# Basic_OCTA-MINI.net
KiCad netlist of a schematic drawn in EAGLE
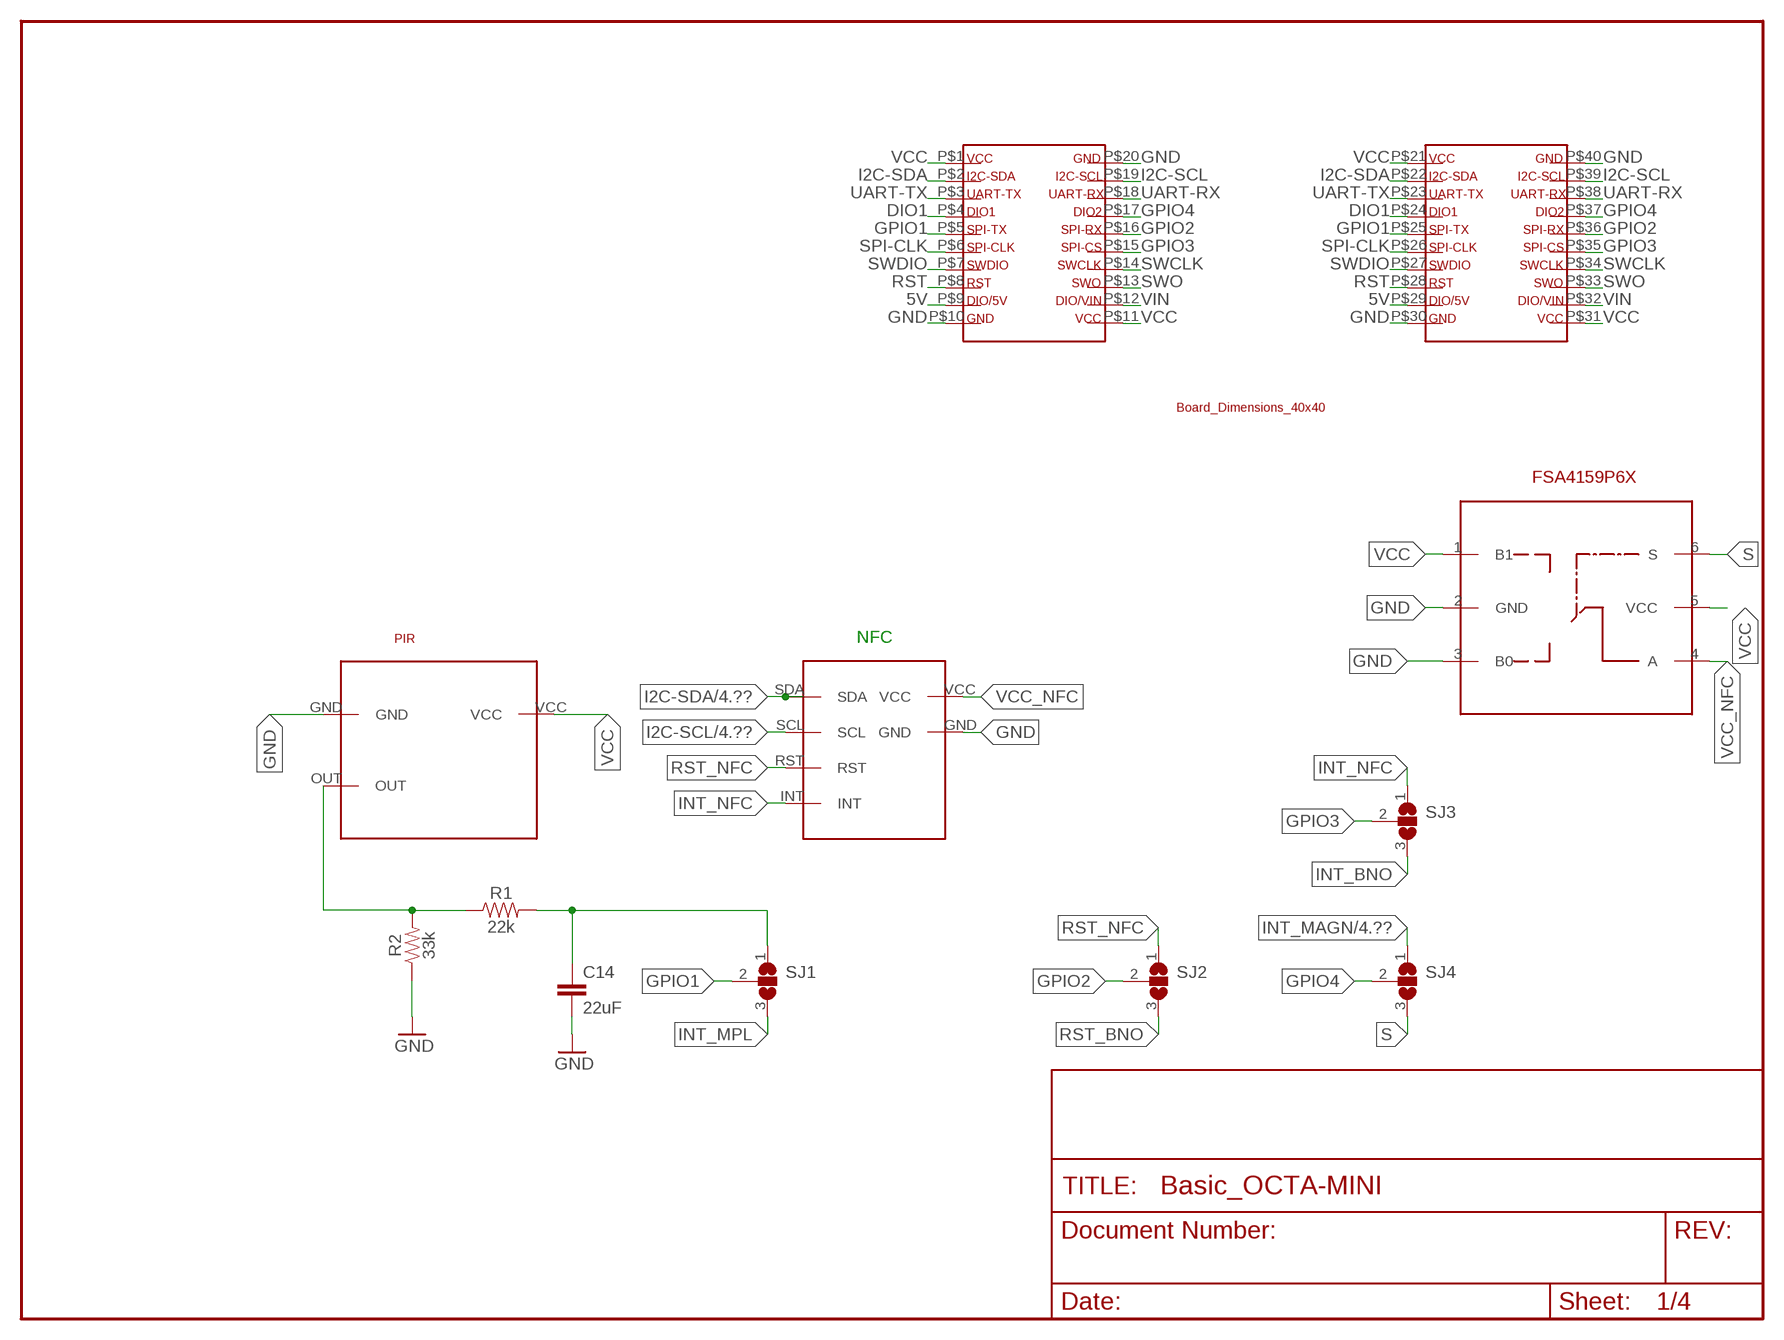
[diagram p0: schematic, sheet 1]
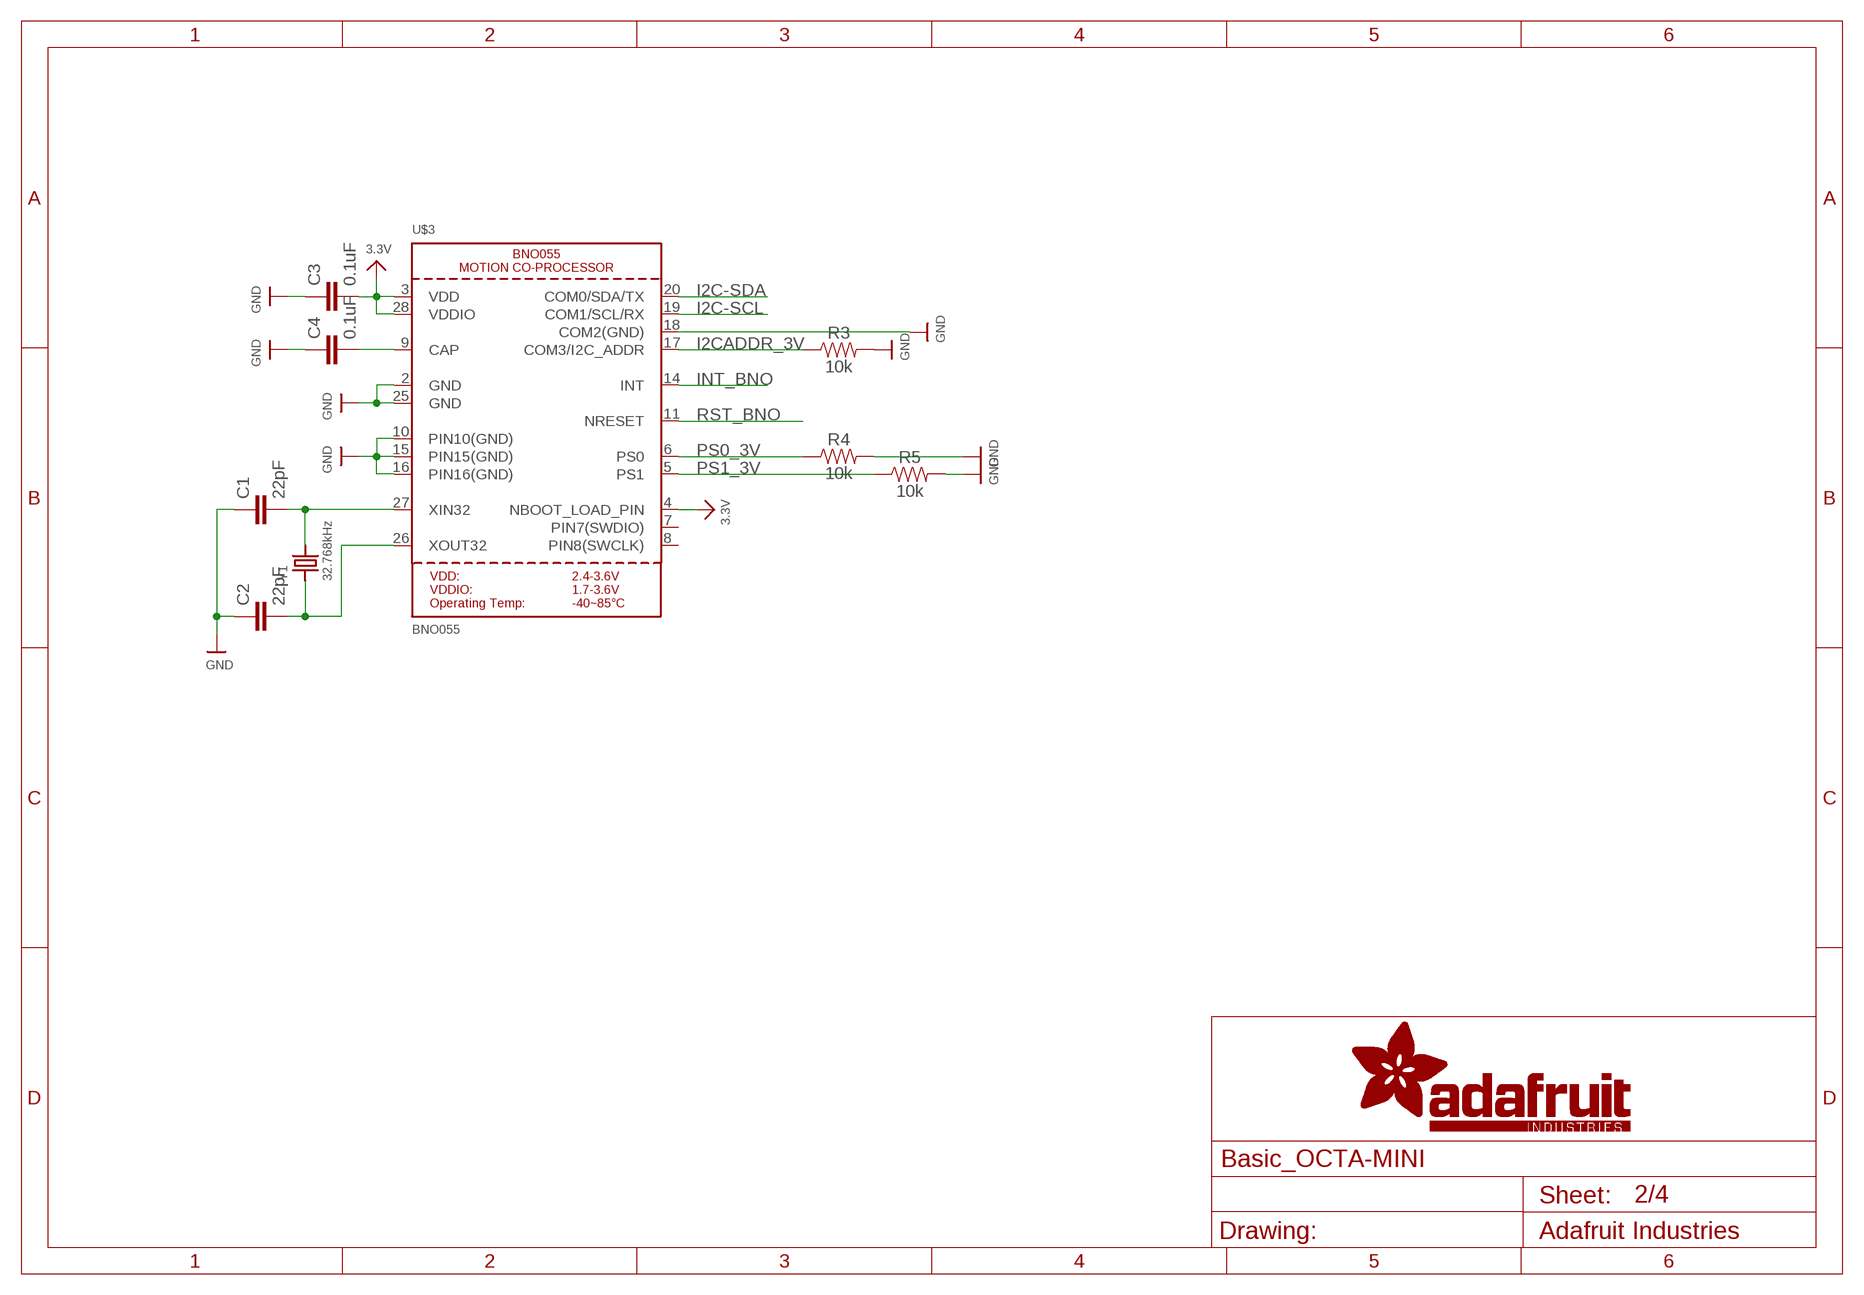
[diagram p1: schematic, sheet 2]
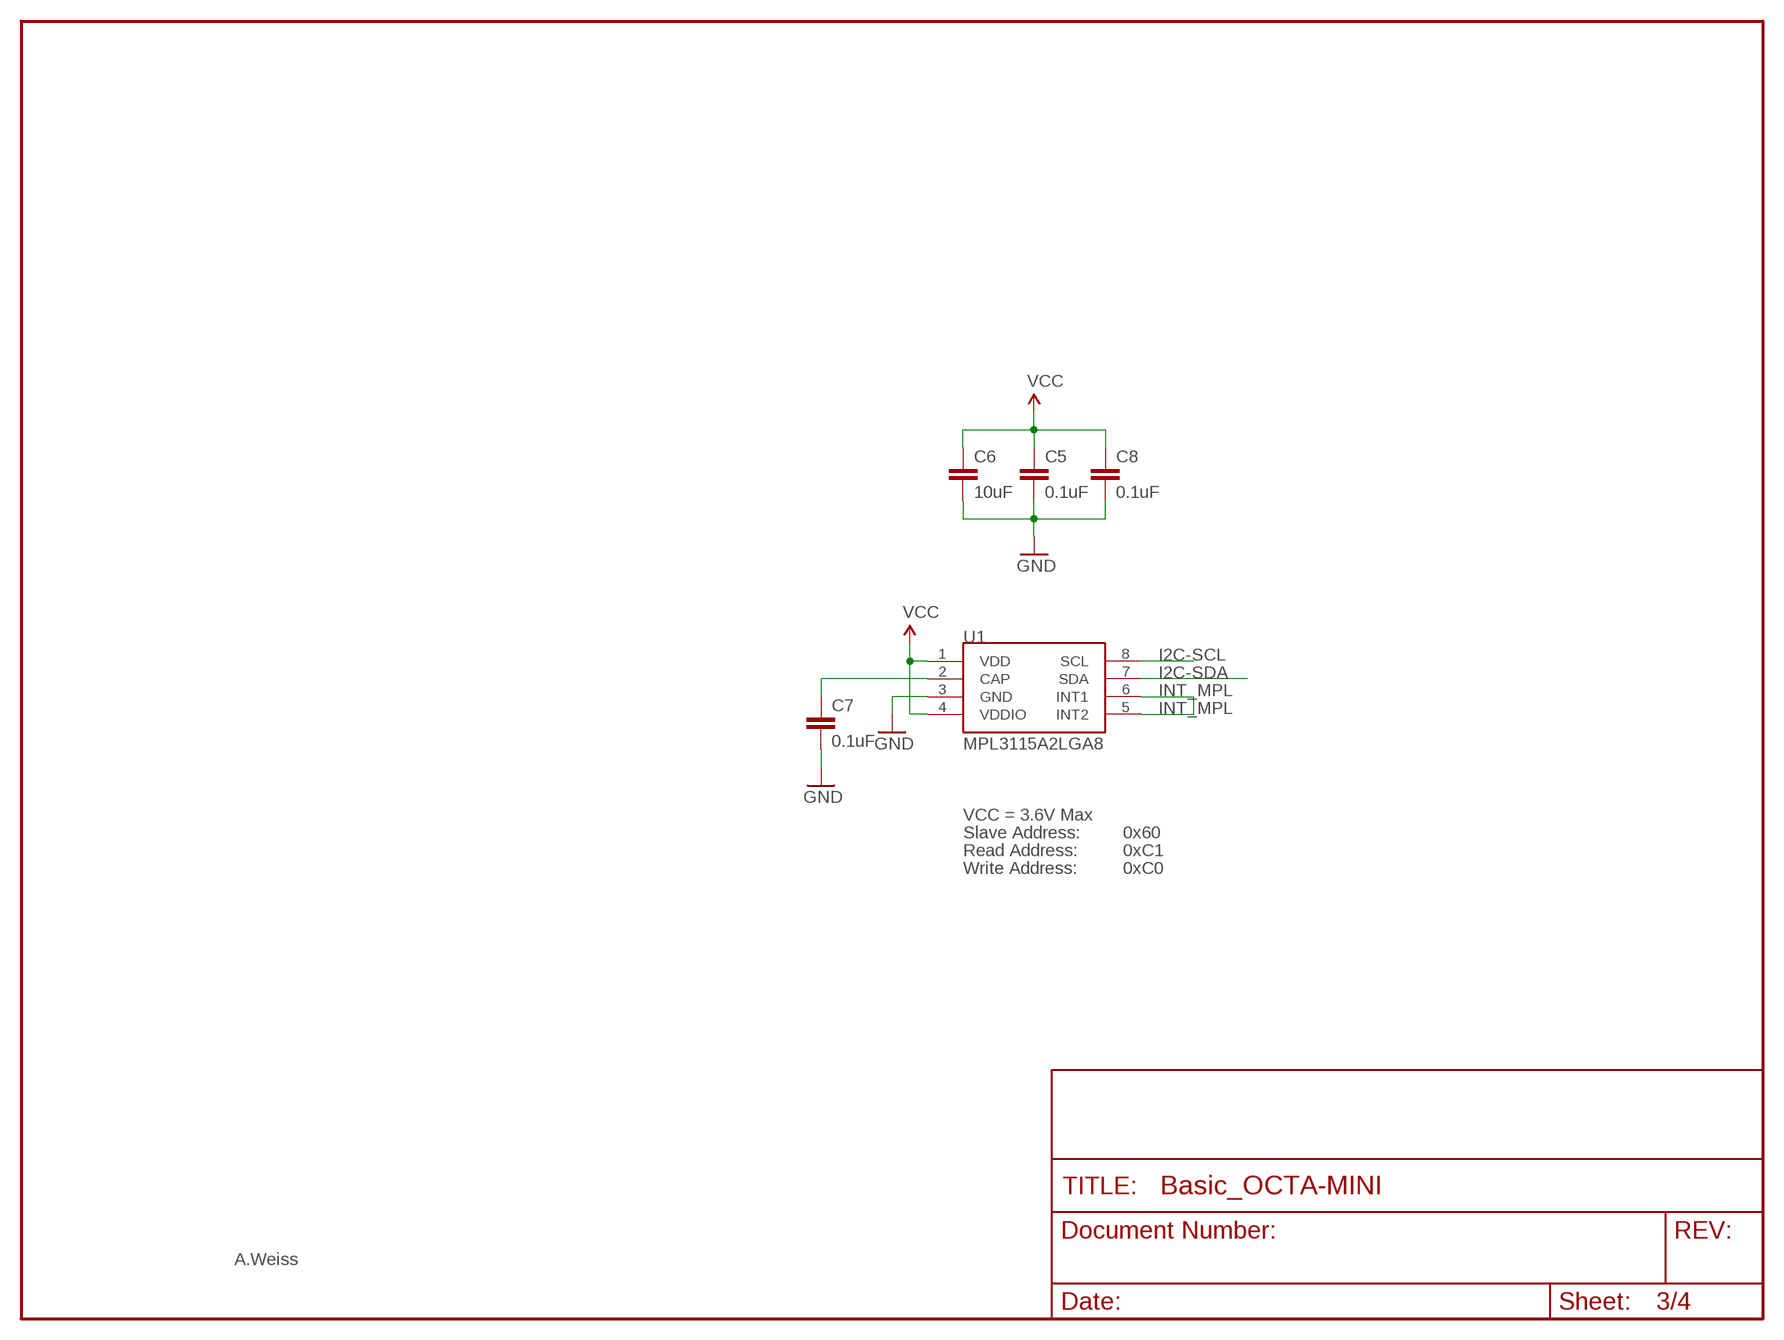
[diagram p2: schematic, sheet 3]
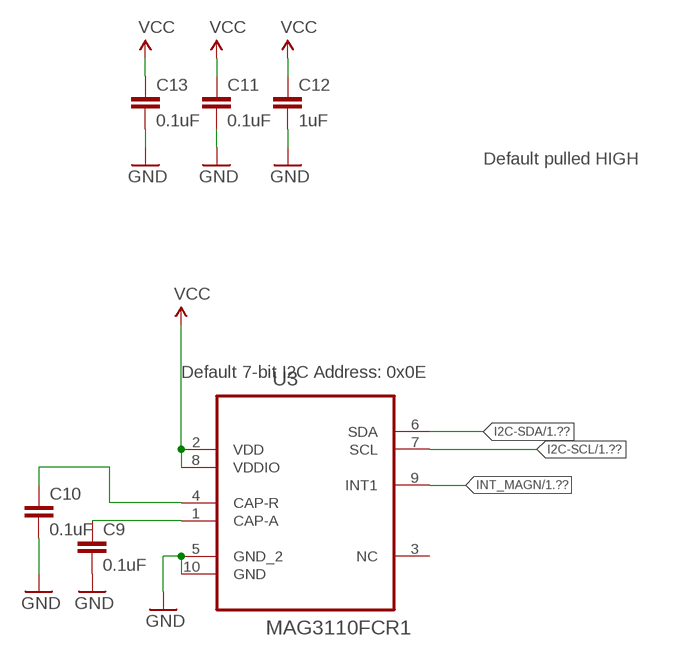
[diagram p3: schematic, sheet 4]

(export (version "E")
  (design (tool "Eeschema 10.0.6"))
  (components
    (comp (ref "C9")
      (value "0.1uF")
      (footprint "eagle-import:0603-CAP")
      (libsource (lib "eagle-import") (part "CAP0603-CAP"))
    )
    (comp (ref "C10")
      (value "0.1uF")
      (footprint "eagle-import:0603-CAP")
      (libsource (lib "eagle-import") (part "CAP0603-CAP"))
    )
    (comp (ref "C11")
      (value "0.1uF")
      (footprint "eagle-import:0603-CAP")
      (libsource (lib "eagle-import") (part "CAP0603-CAP"))
    )
    (comp (ref "C12")
      (value "1uF")
      (footprint "eagle-import:0603-CAP")
      (libsource (lib "eagle-import") (part "CAP0603-CAP"))
    )
    (comp (ref "C13")
      (value "0.1uF")
      (footprint "eagle-import:0603-CAP")
      (libsource (lib "eagle-import") (part "CAP0603-CAP"))
    )
    (comp (ref "U3")
      (value "MAG3110FCR1")
      (footprint "eagle-import:DFN200X200X90-10N")
      (libsource (lib "eagle-import") (part "MAG3110FCR1"))
    )
    (comp (ref "C5")
      (value "0.1uF")
      (footprint "eagle-import:0603")
      (libsource (lib "eagle-import") (part "0.1UF-0603-25V-(+80/-20%)"))
    )
    (comp (ref "C6")
      (value "10uF")
      (footprint "eagle-import:0603")
      (libsource (lib "eagle-import") (part "10UF-0603-6.3V-20%"))
    )
    (comp (ref "C7")
      (value "0.1uF")
      (footprint "eagle-import:0603")
      (libsource (lib "eagle-import") (part "0.1UF-0603-25V-(+80/-20%)"))
    )
    (comp (ref "C8")
      (value "0.1uF")
      (footprint "eagle-import:0603")
      (libsource (lib "eagle-import") (part "0.1UF-0603-25V-(+80/-20%)"))
    )
    (comp (ref "U1")
      (value "MPL3115A2LGA8")
      (footprint "eagle-import:LGA8")
      (libsource (lib "eagle-import") (part "MPL3115A2LGA8"))
    )
    (comp (ref "C1")
      (value "22pF")
      (footprint "eagle-import:0603")
      (libsource (lib "eagle-import") (part "22PF-0603-50V-5%"))
    )
    (comp (ref "C2")
      (value "22pF")
      (footprint "eagle-import:0603")
      (libsource (lib "eagle-import") (part "22PF-0603-50V-5%"))
    )
    (comp (ref "C3")
      (value "0.1uF")
      (footprint "eagle-import:0603")
      (libsource (lib "eagle-import") (part "0.1UF-0603-25V-(+80/-20%)"))
    )
    (comp (ref "C4")
      (value "0.1uF")
      (footprint "eagle-import:0603")
      (libsource (lib "eagle-import") (part "0.1UF-0603-25V-(+80/-20%)"))
    )
    (comp (ref "R3")
      (value "10k")
      (footprint "eagle-import:0603")
      (libsource (lib "eagle-import") (part "10KOHM-0603-1/10W-1%"))
    )
    (comp (ref "R4")
      (value "10k")
      (footprint "eagle-import:0603")
      (libsource (lib "eagle-import") (part "10KOHM-0603-1/10W-1%"))
    )
    (comp (ref "R5")
      (value "10k")
      (footprint "eagle-import:0603")
      (libsource (lib "eagle-import") (part "10KOHM-0603-1/10W-1%"))
    )
    (comp (ref "U$3")
      (value "BNO055")
      (footprint "eagle-import:BNO055")
      (libsource (lib "eagle-import") (part "BNO055"))
    )
    (comp (ref "Y1")
      (value "32.768kHz")
      (footprint "eagle-import:CRYSTAL_8X3.8")
      (libsource (lib "eagle-import") (part "CRYSTAL8.0X3.8"))
    )
    (comp (ref "C14")
      (value "22uF")
      (footprint "eagle-import:0805")
      (libsource (lib "eagle-import") (part "22UF-0805-6.3V-20%"))
    )
    (comp (ref "R1")
      (value "22k")
      (footprint "eagle-import:0603")
      (libsource (lib "eagle-import") (part "22KOHM-0603-1/10W-1%"))
    )
    (comp (ref "R2")
      (value "33k")
      (footprint "eagle-import:0603")
      (libsource (lib "eagle-import") (part "33KOHM-0603-1/10W-1%"))
    )
    (comp (ref "SJ1")
      (value "SJ2W")
      (footprint "eagle-import:SJ_2")
      (libsource (lib "eagle-import") (part "SJ2W"))
    )
    (comp (ref "SJ2")
      (value "SJ2W")
      (footprint "eagle-import:SJ_2")
      (libsource (lib "eagle-import") (part "SJ2W"))
    )
    (comp (ref "SJ3")
      (value "SJ2W")
      (footprint "eagle-import:SJ_2")
      (libsource (lib "eagle-import") (part "SJ2W"))
    )
    (comp (ref "SJ4")
      (value "SJ2W")
      (footprint "eagle-import:SJ_2")
      (libsource (lib "eagle-import") (part "SJ2W"))
    )
    (comp (ref "U$2")
      (value "BOARD-DIMENSIONS-40X40")
      (footprint "eagle-import:BOARD-DIMENSIONS-40X40")
      (libsource (lib "eagle-import") (part "BOARD-DIMENSIONS-40X40"))
    )
    (comp (ref "U$9")
      (value "PIR")
      (footprint "eagle-import:PIR")
      (libsource (lib "eagle-import") (part "PIR"))
    )
    (comp (ref "U$10")
      (value "NFC")
      (footprint "eagle-import:NFC")
      (libsource (lib "eagle-import") (part "NFC"))
    )
    (comp (ref "U$17")
      (value "FSA4159P6X")
      (footprint "eagle-import:SOT65P210X100-6N")
      (libsource (lib "eagle-import") (part "FSA4159P6X"))
    )
  )
  (nets
    (net (code "1") (name "5V") (class "Default")
      (node (ref "U$2") (pin "P$29") (pinfunction "P$29_P$29") (pintype "bidirectional"))
      (node (ref "U$2") (pin "P$9") (pinfunction "P$9_P$9") (pintype "bidirectional"))
    )
    (net (code "2") (name "DIO1") (class "Default")
      (node (ref "U$2") (pin "P$24") (pinfunction "P$24_P$24") (pintype "bidirectional"))
      (node (ref "U$2") (pin "P$4") (pinfunction "P$4_P$4") (pintype "bidirectional"))
    )
    (net (code "3") (name "GND") (class "Default")
      (node (ref "C1") (pin "1") (pinfunction "1_1") (pintype "passive"))
      (node (ref "C10") (pin "2") (pinfunction "2_2") (pintype "passive"))
      (node (ref "C11") (pin "2") (pinfunction "2_2") (pintype "passive"))
      (node (ref "C12") (pin "2") (pinfunction "2_2") (pintype "passive"))
      (node (ref "C13") (pin "2") (pinfunction "2_2") (pintype "passive"))
      (node (ref "C14") (pin "2") (pinfunction "2_2") (pintype "passive"))
      (node (ref "C2") (pin "1") (pinfunction "1_1") (pintype "passive"))
      (node (ref "C3") (pin "1") (pinfunction "1_1") (pintype "passive"))
      (node (ref "C4") (pin "1") (pinfunction "1_1") (pintype "passive"))
      (node (ref "C5") (pin "2") (pinfunction "2_2") (pintype "passive"))
      (node (ref "C6") (pin "2") (pinfunction "2_2") (pintype "passive"))
      (node (ref "C7") (pin "2") (pinfunction "2_2") (pintype "passive"))
      (node (ref "C8") (pin "2") (pinfunction "2_2") (pintype "passive"))
      (node (ref "C9") (pin "2") (pinfunction "2_2") (pintype "passive"))
      (node (ref "R2") (pin "1") (pinfunction "1_1") (pintype "passive"))
      (node (ref "R3") (pin "2") (pinfunction "2_2") (pintype "passive"))
      (node (ref "R4") (pin "2") (pinfunction "2_2") (pintype "passive"))
      (node (ref "R5") (pin "2") (pinfunction "2_2") (pintype "passive"))
      (node (ref "U$10") (pin "GND") (pinfunction "GND_GND") (pintype "bidirectional"))
      (node (ref "U$17") (pin "2") (pinfunction "GND_2") (pintype "bidirectional"))
      (node (ref "U$17") (pin "3") (pinfunction "B0_3") (pintype "bidirectional"))
      (node (ref "U$2") (pin "P$10") (pinfunction "P$10_P$10") (pintype "bidirectional"))
      (node (ref "U$2") (pin "P$20") (pinfunction "P$20_P$20") (pintype "bidirectional"))
      (node (ref "U$2") (pin "P$30") (pinfunction "P$30_P$30") (pintype "bidirectional"))
      (node (ref "U$2") (pin "P$40") (pinfunction "P$40_P$40") (pintype "bidirectional"))
      (node (ref "U$3") (pin "10") (pinfunction "PIN10(GND)_10") (pintype "bidirectional"))
      (node (ref "U$3") (pin "15") (pinfunction "PIN15(GND)_15") (pintype "bidirectional"))
      (node (ref "U$3") (pin "16") (pinfunction "PIN16(GND)_16") (pintype "bidirectional"))
      (node (ref "U$3") (pin "18") (pinfunction "COM2(GND)_18") (pintype "bidirectional"))
      (node (ref "U$3") (pin "2") (pinfunction "GND_2") (pintype "power_in"))
      (node (ref "U$3") (pin "25") (pinfunction "GND_25") (pintype "power_in"))
      (node (ref "U$9") (pin "GND") (pinfunction "GND_GND") (pintype "bidirectional"))
      (node (ref "U1") (pin "3") (pinfunction "GND_3") (pintype "bidirectional"))
      (node (ref "U3") (pin "10") (pinfunction "GND_10") (pintype "power_in"))
      (node (ref "U3") (pin "5") (pinfunction "GND_2_5") (pintype "power_in"))
    )
    (net (code "4") (name "GPIO1") (class "Default")
      (node (ref "SJ1") (pin "2") (pinfunction "2_2") (pintype "passive"))
      (node (ref "U$2") (pin "P$25") (pinfunction "P$25_P$25") (pintype "bidirectional"))
      (node (ref "U$2") (pin "P$5") (pinfunction "P$5_P$5") (pintype "bidirectional"))
    )
    (net (code "5") (name "GPIO2") (class "Default")
      (node (ref "SJ2") (pin "2") (pinfunction "2_2") (pintype "passive"))
      (node (ref "U$2") (pin "P$16") (pinfunction "P$16_P$16") (pintype "bidirectional"))
      (node (ref "U$2") (pin "P$36") (pinfunction "P$36_P$36") (pintype "bidirectional"))
    )
    (net (code "6") (name "GPIO3") (class "Default")
      (node (ref "SJ3") (pin "2") (pinfunction "2_2") (pintype "passive"))
      (node (ref "U$2") (pin "P$15") (pinfunction "P$15_P$15") (pintype "bidirectional"))
      (node (ref "U$2") (pin "P$35") (pinfunction "P$35_P$35") (pintype "bidirectional"))
    )
    (net (code "7") (name "GPIO4") (class "Default")
      (node (ref "SJ4") (pin "2") (pinfunction "2_2") (pintype "passive"))
      (node (ref "U$2") (pin "P$17") (pinfunction "P$17_P$17") (pintype "bidirectional"))
      (node (ref "U$2") (pin "P$37") (pinfunction "P$37_P$37") (pintype "bidirectional"))
    )
    (net (code "8") (name "I2C-SCL") (class "Default")
      (node (ref "U$10") (pin "SCL") (pinfunction "SCL_SCL") (pintype "bidirectional"))
      (node (ref "U$2") (pin "P$19") (pinfunction "P$19_P$19") (pintype "bidirectional"))
      (node (ref "U$2") (pin "P$39") (pinfunction "P$39_P$39") (pintype "bidirectional"))
      (node (ref "U$3") (pin "19") (pinfunction "COM1/SCL/RX_19") (pintype "bidirectional"))
      (node (ref "U1") (pin "8") (pinfunction "SCL_8") (pintype "bidirectional"))
      (node (ref "U3") (pin "7") (pinfunction "SCL_7") (pintype "passive"))
    )
    (net (code "9") (name "I2C-SDA") (class "Default")
      (node (ref "U$10") (pin "SDA") (pinfunction "SDA_SDA") (pintype "bidirectional"))
      (node (ref "U$2") (pin "P$2") (pinfunction "P$2_P$2") (pintype "bidirectional"))
      (node (ref "U$2") (pin "P$22") (pinfunction "P$22_P$22") (pintype "bidirectional"))
      (node (ref "U$3") (pin "20") (pinfunction "COM0/SDA/TX_20") (pintype "bidirectional"))
      (node (ref "U1") (pin "7") (pinfunction "SDA_7") (pintype "bidirectional"))
      (node (ref "U3") (pin "6") (pinfunction "SDA_6") (pintype "passive"))
    )
    (net (code "10") (name "I2CADDR_3V") (class "Default")
      (node (ref "R3") (pin "1") (pinfunction "1_1") (pintype "passive"))
      (node (ref "U$3") (pin "17") (pinfunction "COM3/I2C_ADDR_17") (pintype "bidirectional"))
    )
    (net (code "11") (name "INT_BNO") (class "Default")
      (node (ref "SJ3") (pin "3") (pinfunction "3_3") (pintype "passive"))
      (node (ref "U$3") (pin "14") (pinfunction "INT_14") (pintype "output"))
    )
    (net (code "12") (name "INT_MAGN") (class "Default")
      (node (ref "SJ4") (pin "1") (pinfunction "1_1") (pintype "passive"))
      (node (ref "U3") (pin "9") (pinfunction "INT1_9") (pintype "output"))
    )
    (net (code "13") (name "INT_MPL") (class "Default")
      (node (ref "SJ1") (pin "3") (pinfunction "3_3") (pintype "passive"))
      (node (ref "U1") (pin "5") (pinfunction "INT2_5") (pintype "bidirectional"))
      (node (ref "U1") (pin "6") (pinfunction "INT1_6") (pintype "bidirectional"))
    )
    (net (code "14") (name "INT_NFC") (class "Default")
      (node (ref "SJ3") (pin "1") (pinfunction "1_1") (pintype "passive"))
      (node (ref "U$10") (pin "INT") (pinfunction "INT_INT") (pintype "bidirectional"))
    )
    (net (code "15") (name "Net-(C14-Pad1)") (class "Default")
      (node (ref "C14") (pin "1") (pinfunction "1_1") (pintype "passive"))
      (node (ref "R1") (pin "2") (pinfunction "2_2") (pintype "passive"))
      (node (ref "SJ1") (pin "1") (pinfunction "1_1") (pintype "passive"))
    )
    (net (code "16") (name "Net-(R1-Pad1)") (class "Default")
      (node (ref "R1") (pin "1") (pinfunction "1_1") (pintype "passive"))
      (node (ref "R2") (pin "2") (pinfunction "2_2") (pintype "passive"))
      (node (ref "U$9") (pin "OUT") (pinfunction "OUT_OUT") (pintype "bidirectional"))
    )
    (net (code "17") (name "Net-(U$3-CAP)") (class "Default")
      (node (ref "C4") (pin "2") (pinfunction "2_2") (pintype "passive"))
      (node (ref "U$3") (pin "9") (pinfunction "CAP_9") (pintype "passive"))
    )
    (net (code "18") (name "Net-(U$3-XIN32)") (class "Default")
      (node (ref "C1") (pin "2") (pinfunction "2_2") (pintype "passive"))
      (node (ref "U$3") (pin "27") (pinfunction "XIN32_27") (pintype "input"))
      (node (ref "Y1") (pin "P$4") (pinfunction "2_P$4") (pintype "passive"))
    )
    (net (code "19") (name "Net-(U$3-XOUT32)") (class "Default")
      (node (ref "C2") (pin "2") (pinfunction "2_2") (pintype "passive"))
      (node (ref "U$3") (pin "26") (pinfunction "XOUT32_26") (pintype "output"))
      (node (ref "Y1") (pin "P$1") (pinfunction "1_P$1") (pintype "passive"))
    )
    (net (code "20") (name "Net-(U1-CAP)") (class "Default")
      (node (ref "C7") (pin "1") (pinfunction "1_1") (pintype "passive"))
      (node (ref "U1") (pin "2") (pinfunction "CAP_2") (pintype "bidirectional"))
    )
    (net (code "21") (name "Net-(U3-CAP-A)") (class "Default")
      (node (ref "C9") (pin "1") (pinfunction "1_1") (pintype "passive"))
      (node (ref "U3") (pin "1") (pinfunction "CAP-A_1") (pintype "passive"))
    )
    (net (code "22") (name "Net-(U3-CAP-R)") (class "Default")
      (node (ref "C10") (pin "1") (pinfunction "1_1") (pintype "passive"))
      (node (ref "U3") (pin "4") (pinfunction "CAP-R_4") (pintype "passive"))
    )
    (net (code "23") (name "PS0_3V") (class "Default")
      (node (ref "R4") (pin "1") (pinfunction "1_1") (pintype "passive"))
      (node (ref "U$3") (pin "6") (pinfunction "PS0_6") (pintype "input"))
    )
    (net (code "24") (name "PS1_3V") (class "Default")
      (node (ref "R5") (pin "1") (pinfunction "1_1") (pintype "passive"))
      (node (ref "U$3") (pin "5") (pinfunction "PS1_5") (pintype "input"))
    )
    (net (code "25") (name "RST") (class "Default")
      (node (ref "U$2") (pin "P$28") (pinfunction "P$28_P$28") (pintype "bidirectional"))
      (node (ref "U$2") (pin "P$8") (pinfunction "P$8_P$8") (pintype "bidirectional"))
    )
    (net (code "26") (name "RST_BNO") (class "Default")
      (node (ref "SJ2") (pin "3") (pinfunction "3_3") (pintype "passive"))
      (node (ref "U$3") (pin "11") (pinfunction "NRESET_11") (pintype "bidirectional"))
    )
    (net (code "27") (name "RST_NFC") (class "Default")
      (node (ref "SJ2") (pin "1") (pinfunction "1_1") (pintype "passive"))
      (node (ref "U$10") (pin "RST") (pinfunction "RST_RST") (pintype "bidirectional"))
    )
    (net (code "28") (name "S") (class "Default")
      (node (ref "SJ4") (pin "3") (pinfunction "3_3") (pintype "passive"))
      (node (ref "U$17") (pin "6") (pinfunction "S_6") (pintype "bidirectional"))
    )
    (net (code "29") (name "SPI-CLK") (class "Default")
      (node (ref "U$2") (pin "P$26") (pinfunction "P$26_P$26") (pintype "bidirectional"))
      (node (ref "U$2") (pin "P$6") (pinfunction "P$6_P$6") (pintype "bidirectional"))
    )
    (net (code "30") (name "SWCLK") (class "Default")
      (node (ref "U$2") (pin "P$14") (pinfunction "P$14_P$14") (pintype "bidirectional"))
      (node (ref "U$2") (pin "P$34") (pinfunction "P$34_P$34") (pintype "bidirectional"))
    )
    (net (code "31") (name "SWDIO") (class "Default")
      (node (ref "U$2") (pin "P$27") (pinfunction "P$27_P$27") (pintype "bidirectional"))
      (node (ref "U$2") (pin "P$7") (pinfunction "P$7_P$7") (pintype "bidirectional"))
    )
    (net (code "32") (name "SWO") (class "Default")
      (node (ref "U$2") (pin "P$13") (pinfunction "P$13_P$13") (pintype "bidirectional"))
      (node (ref "U$2") (pin "P$33") (pinfunction "P$33_P$33") (pintype "bidirectional"))
    )
    (net (code "33") (name "UART-RX") (class "Default")
      (node (ref "U$2") (pin "P$18") (pinfunction "P$18_P$18") (pintype "bidirectional"))
      (node (ref "U$2") (pin "P$38") (pinfunction "P$38_P$38") (pintype "bidirectional"))
    )
    (net (code "34") (name "UART-TX") (class "Default")
      (node (ref "U$2") (pin "P$23") (pinfunction "P$23_P$23") (pintype "bidirectional"))
      (node (ref "U$2") (pin "P$3") (pinfunction "P$3_P$3") (pintype "bidirectional"))
    )
    (net (code "35") (name "VCC") (class "Default")
      (node (ref "C11") (pin "1") (pinfunction "1_1") (pintype "passive"))
      (node (ref "C12") (pin "1") (pinfunction "1_1") (pintype "passive"))
      (node (ref "C13") (pin "1") (pinfunction "1_1") (pintype "passive"))
      (node (ref "C3") (pin "2") (pinfunction "2_2") (pintype "passive"))
      (node (ref "C5") (pin "1") (pinfunction "1_1") (pintype "passive"))
      (node (ref "C6") (pin "1") (pinfunction "1_1") (pintype "passive"))
      (node (ref "C8") (pin "1") (pinfunction "1_1") (pintype "passive"))
      (node (ref "U$17") (pin "1") (pinfunction "B1_1") (pintype "bidirectional"))
      (node (ref "U$17") (pin "5") (pinfunction "VCC_5") (pintype "bidirectional"))
      (node (ref "U$2") (pin "P$1") (pinfunction "P$1_P$1") (pintype "bidirectional"))
      (node (ref "U$2") (pin "P$11") (pinfunction "P$11_P$11") (pintype "bidirectional"))
      (node (ref "U$2") (pin "P$21") (pinfunction "P$21_P$21") (pintype "bidirectional"))
      (node (ref "U$2") (pin "P$31") (pinfunction "P$31_P$31") (pintype "bidirectional"))
      (node (ref "U$3") (pin "28") (pinfunction "VDDIO_28") (pintype "power_in"))
      (node (ref "U$3") (pin "3") (pinfunction "VDD_3") (pintype "power_in"))
      (node (ref "U$3") (pin "4") (pinfunction "NBOOT_LOAD_PIN_4") (pintype "bidirectional"))
      (node (ref "U$9") (pin "VCC") (pinfunction "VCC_VCC") (pintype "bidirectional"))
      (node (ref "U1") (pin "1") (pinfunction "VDD_1") (pintype "bidirectional"))
      (node (ref "U1") (pin "4") (pinfunction "VDDIO_4") (pintype "bidirectional"))
      (node (ref "U3") (pin "2") (pinfunction "VDD_2") (pintype "power_in"))
      (node (ref "U3") (pin "8") (pinfunction "VDDIO_8") (pintype "power_in"))
    )
    (net (code "36") (name "VCC_NFC") (class "Default")
      (node (ref "U$10") (pin "VCC") (pinfunction "VCC_VCC") (pintype "bidirectional"))
      (node (ref "U$17") (pin "4") (pinfunction "A_4") (pintype "bidirectional"))
    )
    (net (code "37") (name "VIN") (class "Default")
      (node (ref "U$2") (pin "P$12") (pinfunction "P$12_P$12") (pintype "bidirectional"))
      (node (ref "U$2") (pin "P$32") (pinfunction "P$32_P$32") (pintype "bidirectional"))
    )
    (net (code "38") (name "unconnected-(U$3-PIN7(SWDIO)-Pad7)") (class "Default")
      (node (ref "U$3") (pin "7") (pinfunction "PIN7(SWDIO)_7") (pintype "bidirectional"))
    )
    (net (code "39") (name "unconnected-(U$3-PIN8(SWCLK)-Pad8)") (class "Default")
      (node (ref "U$3") (pin "8") (pinfunction "PIN8(SWCLK)_8") (pintype "bidirectional"))
    )
    (net (code "40") (name "unconnected-(U3-NC-Pad3)") (class "Default")
      (node (ref "U3") (pin "3") (pinfunction "NC_3") (pintype "no_connect"))
    )
  )
)
